# psram.net
KiCad netlist of a schematic drawn in Altium Designer
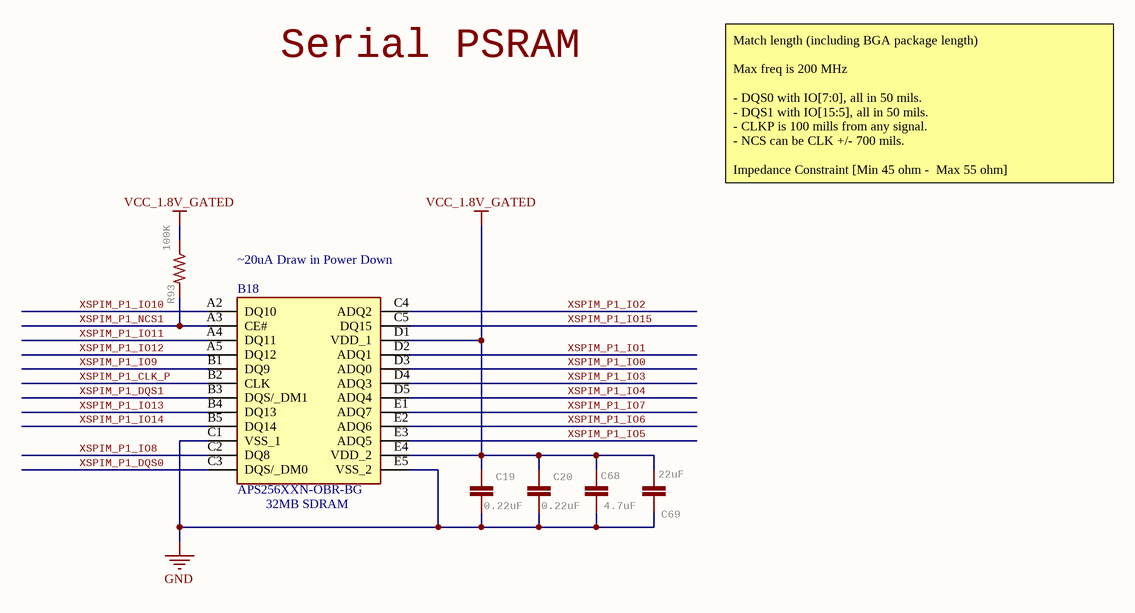
[diagram p0: psram.SchDoc]

(export (version "E")
  (design (tool "Eeschema 10.0.6"))
  (components
    (comp (ref "B18")
      (value "APS256XXN-OBR-BG")
      (footprint "24-TBGA")
      (description "DRAM IoT RAM 256Mb OPI (x8,x16) DDR 200MHz, 1.8V, Ind. Temp., BGA24")
      (fields (field (name "MOUSER PART NUMBER") "878-APS256XXN-OBR-BG"))
      (libsource (lib "APS256XXN-OBR-BG") (part "APS256XXN-OBR-BG"))
    )
    (comp (ref "C19")
      (value "0.22uF")
      (footprint "C0201")
      (description "CAPACITOR, European symbol")
      (fields (field (name "MPN") "GRM033R60J224ME15D"))
      (libsource (lib "rt10") (part "C-EUC0201"))
    )
    (comp (ref "C20")
      (value "0.22uF")
      (footprint "C0201")
      (description "CAPACITOR, European symbol")
      (fields (field (name "MPN") "GRM033R60J224ME15D"))
      (libsource (lib "rt10") (part "C-EUC0201"))
    )
    (comp (ref "C68")
      (value "4.7uF")
      (footprint "0402-CAP")
      (description "CapacitorStandard 0603 ceramic capacitor, and 0.1\" leaded capacitor.")
      (fields (field (name "MPN") "JMK105BBJ475MV-F"))
      (libsource (lib "openmv-ae3") (part "CAP0402-CAP"))
    )
    (comp (ref "C69")
      (value "22uF")
      (footprint "0805")
      (fields (field (name "MPN") "CL21A226MQQNNNE"))
      (libsource (lib "openmv-ae3") (part "22UF-0805-6.3V-20%"))
    )
    (comp (ref "R93")
      (value "100K")
      (footprint "0402-RES")
      (description "ResistorBasic schematic elements and footprints for 0603, 1206, and PTH resistors.")
      (fields (field (name "MPN") "AC0402FR-07100KL"))
      (libsource (lib "openmv-ae3") (part "RESISTOR0402-RES"))
    )
  )
  (nets
    (net (code "1") (name "/XSPIM_P1_CLK_P") (class "Default")
      (node (ref "B18") (pin "B2") (pinfunction "CLK_B2") (pintype "passive"))
    )
    (net (code "2") (name "/XSPIM_P1_DQS0") (class "Default")
      (node (ref "B18") (pin "C3") (pinfunction "DQS/_DM0_C3") (pintype "passive"))
    )
    (net (code "3") (name "/XSPIM_P1_DQS1") (class "Default")
      (node (ref "B18") (pin "B3") (pinfunction "DQS/_DM1_B3") (pintype "passive"))
    )
    (net (code "4") (name "/XSPIM_P1_IO0") (class "Default")
      (node (ref "B18") (pin "D3") (pinfunction "ADQ0_D3") (pintype "passive"))
    )
    (net (code "5") (name "/XSPIM_P1_IO1") (class "Default")
      (node (ref "B18") (pin "D2") (pinfunction "ADQ1_D2") (pintype "passive"))
    )
    (net (code "6") (name "/XSPIM_P1_IO2") (class "Default")
      (node (ref "B18") (pin "C4") (pinfunction "ADQ2_C4") (pintype "passive"))
    )
    (net (code "7") (name "/XSPIM_P1_IO3") (class "Default")
      (node (ref "B18") (pin "D4") (pinfunction "ADQ3_D4") (pintype "passive"))
    )
    (net (code "8") (name "/XSPIM_P1_IO4") (class "Default")
      (node (ref "B18") (pin "D5") (pinfunction "ADQ4_D5") (pintype "passive"))
    )
    (net (code "9") (name "/XSPIM_P1_IO5") (class "Default")
      (node (ref "B18") (pin "E3") (pinfunction "ADQ5_E3") (pintype "passive"))
    )
    (net (code "10") (name "/XSPIM_P1_IO6") (class "Default")
      (node (ref "B18") (pin "E2") (pinfunction "ADQ6_E2") (pintype "passive"))
    )
    (net (code "11") (name "/XSPIM_P1_IO7") (class "Default")
      (node (ref "B18") (pin "E1") (pinfunction "ADQ7_E1") (pintype "passive"))
    )
    (net (code "12") (name "/XSPIM_P1_IO8") (class "Default")
      (node (ref "B18") (pin "C2") (pinfunction "DQ8_C2") (pintype "passive"))
    )
    (net (code "13") (name "/XSPIM_P1_IO9") (class "Default")
      (node (ref "B18") (pin "B1") (pinfunction "DQ9_B1") (pintype "passive"))
    )
    (net (code "14") (name "/XSPIM_P1_IO10") (class "Default")
      (node (ref "B18") (pin "A2") (pinfunction "DQ10_A2") (pintype "passive"))
    )
    (net (code "15") (name "/XSPIM_P1_IO11") (class "Default")
      (node (ref "B18") (pin "A4") (pinfunction "DQ11_A4") (pintype "passive"))
    )
    (net (code "16") (name "/XSPIM_P1_IO12") (class "Default")
      (node (ref "B18") (pin "A5") (pinfunction "DQ12_A5") (pintype "passive"))
    )
    (net (code "17") (name "/XSPIM_P1_IO13") (class "Default")
      (node (ref "B18") (pin "B4") (pinfunction "DQ13_B4") (pintype "passive"))
    )
    (net (code "18") (name "/XSPIM_P1_IO14") (class "Default")
      (node (ref "B18") (pin "B5") (pinfunction "DQ14_B5") (pintype "passive"))
    )
    (net (code "19") (name "/XSPIM_P1_IO15") (class "Default")
      (node (ref "B18") (pin "C5") (pinfunction "DQ15_C5") (pintype "passive"))
    )
    (net (code "20") (name "/XSPIM_P1_NCS1") (class "Default")
      (node (ref "B18") (pin "A3") (pinfunction "CE#_A3") (pintype "passive"))
      (node (ref "R93") (pin "2") (pinfunction "2_2") (pintype "passive"))
    )
    (net (code "21") (name "GND") (class "Default")
      (node (ref "B18") (pin "C1") (pinfunction "VSS_1_C1") (pintype "passive"))
      (node (ref "B18") (pin "E5") (pinfunction "VSS_2_E5") (pintype "passive"))
      (node (ref "C19") (pin "2") (pinfunction "2_2") (pintype "passive"))
      (node (ref "C20") (pin "2") (pinfunction "2_2") (pintype "passive"))
      (node (ref "C68") (pin "1") (pinfunction "1_1") (pintype "passive"))
      (node (ref "C69") (pin "2") (pinfunction "2_2") (pintype "passive"))
    )
    (net (code "22") (name "VCC_1.8V_GATED") (class "Default")
      (node (ref "B18") (pin "D1") (pinfunction "VDD_1_D1") (pintype "passive"))
      (node (ref "B18") (pin "E4") (pinfunction "VDD_2_E4") (pintype "passive"))
      (node (ref "C19") (pin "1") (pinfunction "1_1") (pintype "passive"))
      (node (ref "C20") (pin "1") (pinfunction "1_1") (pintype "passive"))
      (node (ref "C68") (pin "2") (pinfunction "2_2") (pintype "passive"))
      (node (ref "C69") (pin "1") (pinfunction "1_1") (pintype "passive"))
      (node (ref "R93") (pin "1") (pinfunction "1_1") (pintype "passive"))
    )
  )
)
